# Output.net
KiCad netlist of a schematic drawn in Altium Designer
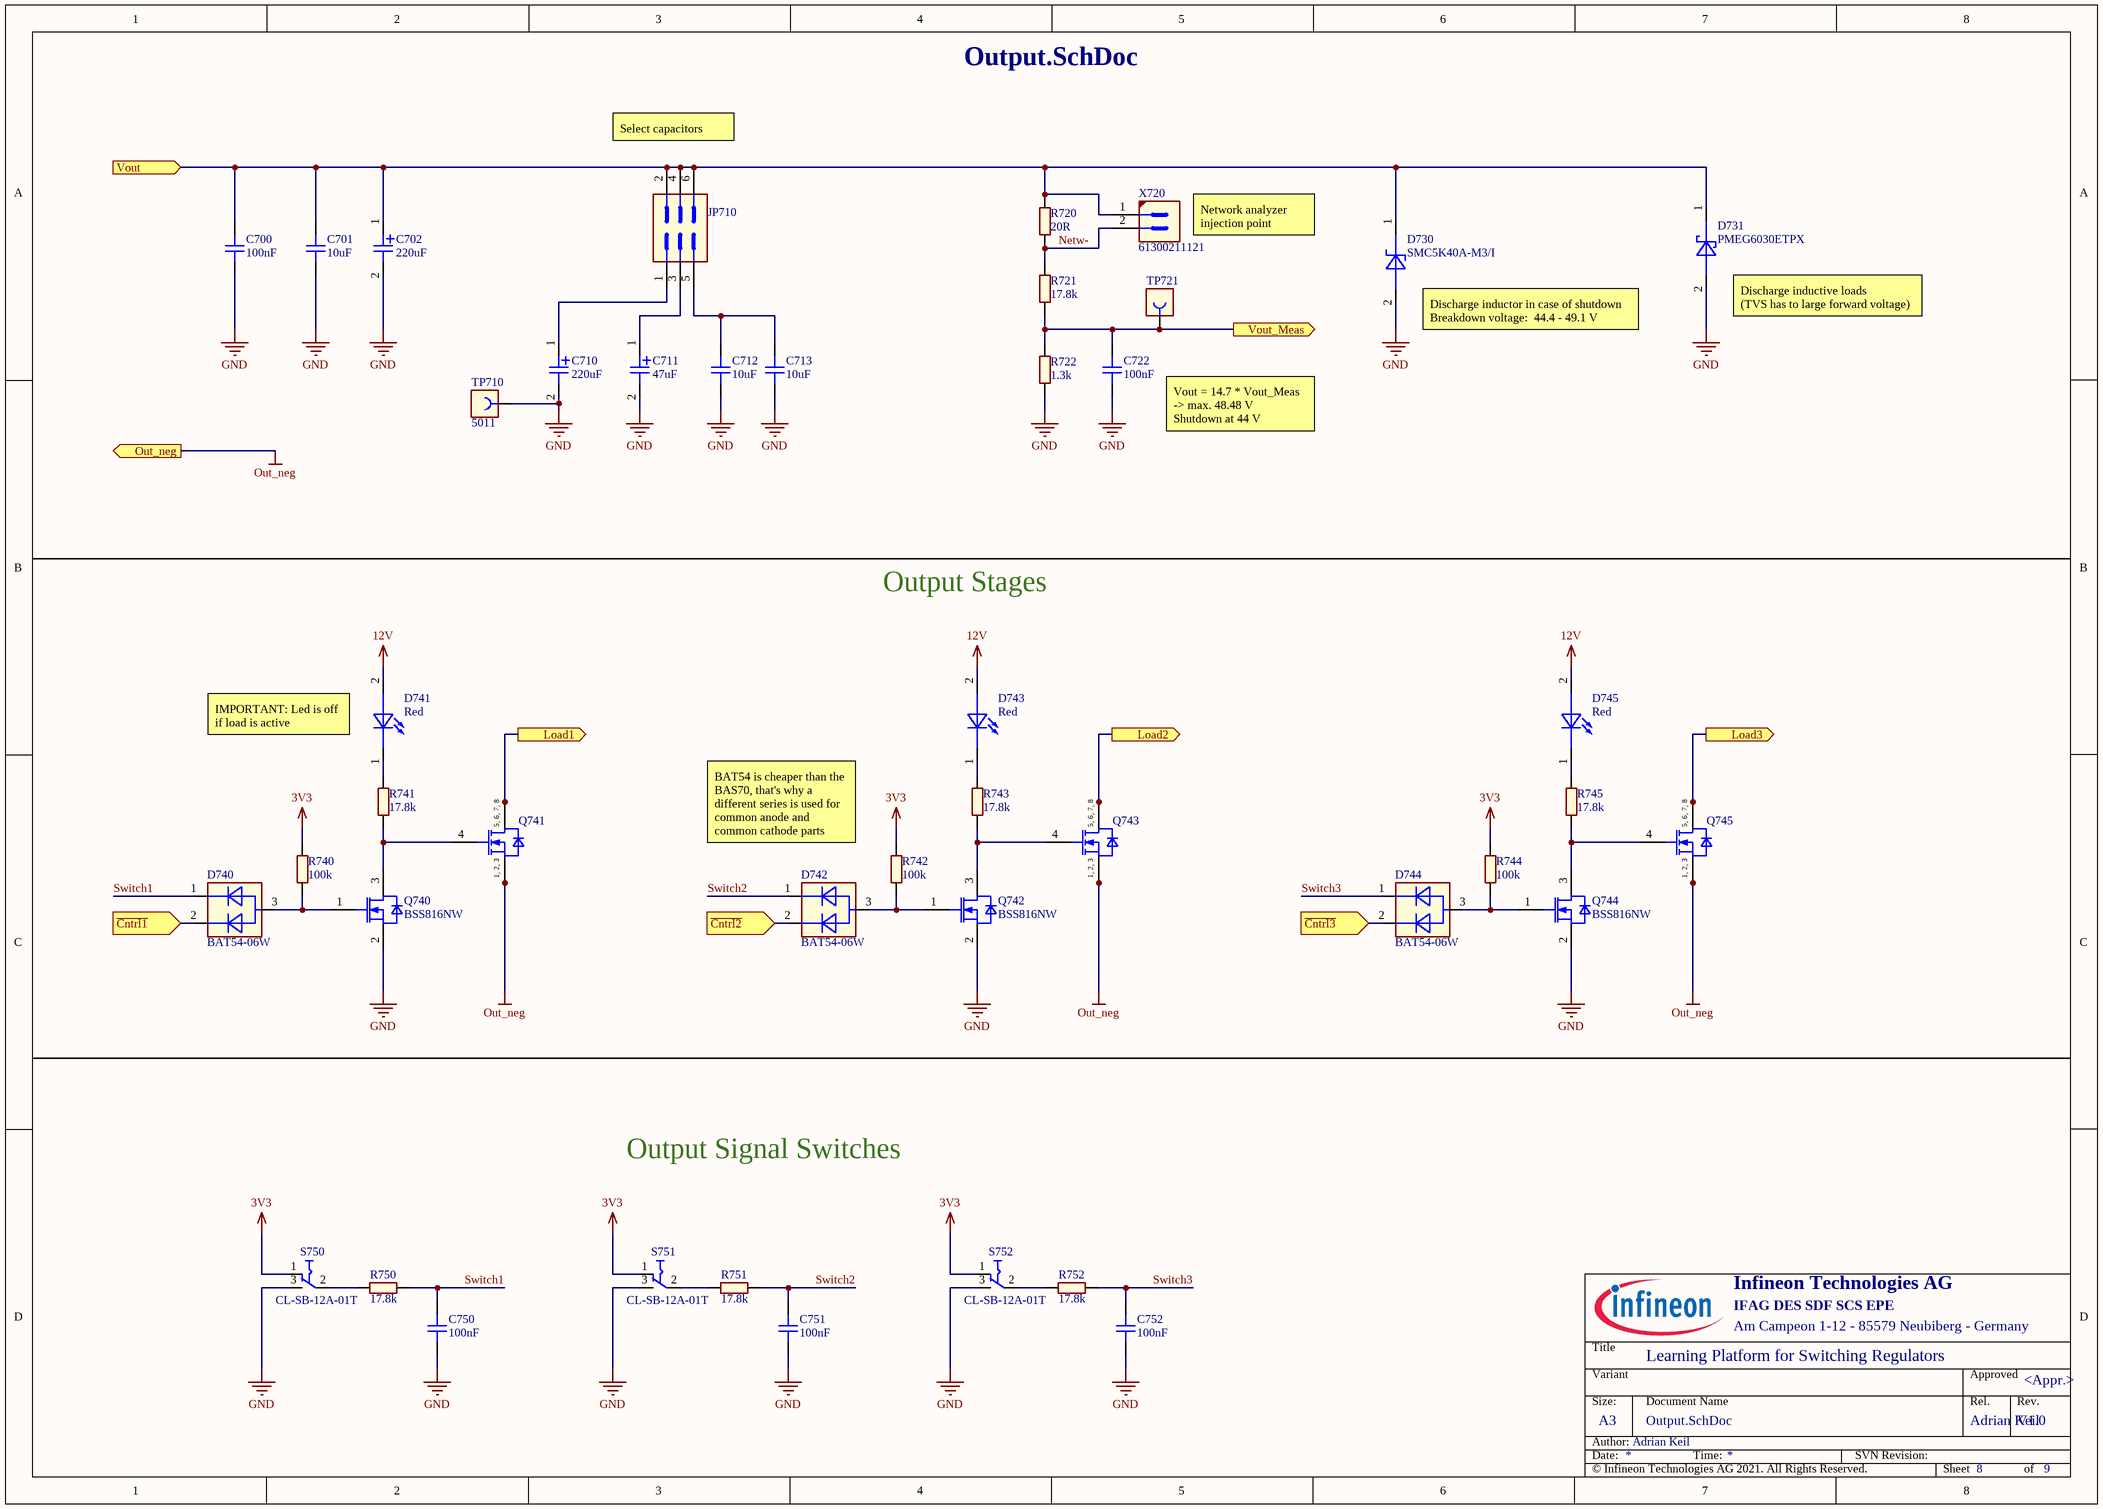
[diagram p0: Output.SchDoc]

(export (version "E")
  (design (tool "Eeschema 10.0.6"))
  (components
    (comp (ref "C700")
      (value "100nF")
      (footprint "CAPC1608X90N-2")
      (description "CAP / CERA / 100nF / 50V / 10% / X7R (EIA) / -55°C to 125°C / 0603 / SMD / -")
      (fields (field (name "MANUFACTURER") "AVX"))
      (libsource (lib "PCBLibraryData") (part "CAP-SGL-STD-02P_00000001"))
    )
    (comp (ref "C701")
      (value "10uF")
      (footprint "CAPC3216X190N-1")
      (description "CAP / CERA / 10uF / 50V / 20% / X5R (EIA) / -55°C to 85°C / 1206 (3216) / SMD / -")
      (fields (field (name "MANUFACTURER") "Taiyo Yuden"))
      (libsource (lib "PCBLibraryData") (part "CAP-SGL-STD-02P_00000001"))
    )
    (comp (ref "C702")
      (value "220uF")
      (footprint "CAPAE1030X1050N-2")
      (fields (field (name "MANUFACTURER") "Wurth Elektronik"))
      (libsource (lib "PCBLibraryData") (part "CAP-SGL-POL-02P_00000002"))
    )
    (comp (ref "C710")
      (value "220uF")
      (footprint "CAPAE1030X1050N-2")
      (fields (field (name "MANUFACTURER") "Wurth Elektronik"))
      (libsource (lib "PCBLibraryData") (part "CAP-SGL-POL-02P_00000002"))
    )
    (comp (ref "C711")
      (value "47uF")
      (footprint "CAPAE660X770N")
      (fields (field (name "MANUFACTURER") "Wurth Elektronik"))
      (libsource (lib "PCBLibraryData") (part "CAP-SGL-POL-02P_00000002"))
    )
    (comp (ref "C712")
      (value "10uF")
      (footprint "CAPC3216X190N-1")
      (description "CAP / CERA / 10uF / 50V / 20% / X5R (EIA) / -55°C to 85°C / 1206 (3216) / SMD / -")
      (fields (field (name "MANUFACTURER") "Taiyo Yuden"))
      (libsource (lib "PCBLibraryData") (part "CAP-SGL-STD-02P_00000001"))
    )
    (comp (ref "C713")
      (value "10uF")
      (footprint "CAPC3216X190N-1")
      (description "CAP / CERA / 10uF / 50V / 20% / X5R (EIA) / -55°C to 85°C / 1206 (3216) / SMD / -")
      (fields (field (name "MANUFACTURER") "Taiyo Yuden"))
      (libsource (lib "PCBLibraryData") (part "CAP-SGL-STD-02P_00000001"))
    )
    (comp (ref "C722")
      (value "100nF")
      (footprint "CAPC1608X90N-2")
      (description "CAP / CERA / 100nF / 50V / 10% / X7R (EIA) / -55°C to 125°C / 0603 / SMD / -")
      (fields (field (name "MANUFACTURER") "AVX"))
      (libsource (lib "PCBLibraryData") (part "CAP-SGL-STD-02P_00000001"))
    )
    (comp (ref "C750")
      (value "100nF")
      (footprint "CAPC1608X90N-2")
      (description "CAP / CERA / 100nF / 50V / 10% / X7R (EIA) / -55°C to 125°C / 0603 / SMD / -")
      (fields (field (name "MANUFACTURER") "AVX"))
      (libsource (lib "PCBLibraryData") (part "CAP-SGL-STD-02P_00000001"))
    )
    (comp (ref "C751")
      (value "100nF")
      (footprint "CAPC1608X90N-2")
      (description "CAP / CERA / 100nF / 50V / 10% / X7R (EIA) / -55°C to 125°C / 0603 / SMD / -")
      (fields (field (name "MANUFACTURER") "AVX"))
      (libsource (lib "PCBLibraryData") (part "CAP-SGL-STD-02P_00000001"))
    )
    (comp (ref "C752")
      (value "100nF")
      (footprint "CAPC1608X90N-2")
      (description "CAP / CERA / 100nF / 50V / 10% / X7R (EIA) / -55°C to 125°C / 0603 / SMD / -")
      (fields (field (name "MANUFACTURER") "AVX"))
      (libsource (lib "PCBLibraryData") (part "CAP-SGL-STD-02P_00000001"))
    )
    (comp (ref "D730")
      (value "SMC5K40A-M3/I")
      (footprint "DIOM7959X262N")
      (description "Surface Mount Transient Voltage Suppressors, Unidirectional, Very Fast Response Time")
      (fields (field (name "MANUFACTURER") "Vishay"))
      (libsource (lib "PCBLibraryData") (part "d_tvs_a"))
    )
    (comp (ref "D731")
      (value "PMEG6030ETPX")
      (footprint "SODFL4725X110N")
      (description "DIODE SCHOTTKY 60V 3A SOD128")
      (fields (field (name "MANUFACTURER") "Nexperia"))
      (libsource (lib "PCBLibraryData") (part "d_schottky_a"))
    )
    (comp (ref "D740")
      (value "BAT54-06W")
      (footprint "SOT65P210X100-3N-1-V")
      (description "Silicon Schottky Diodes")
      (fields (field (name "MANUFACTURER") "Infineon Technologies"))
      (libsource (lib "PCBLibraryData") (part "d_dual_c1c2a3_3p"))
    )
    (comp (ref "D741")
      (value "Red")
      (footprint "LEDSC160X80X80-2N-1")
      (description "WL-SMCW SMT Mono-color Chip LED Waterclear, Red,630nm")
      (fields (field (name "MANUFACTURER") "Wurth Elektronik"))
      (libsource (lib "PCBLibraryData") (part "d_led_a"))
    )
    (comp (ref "D742")
      (value "BAT54-06W")
      (footprint "SOT65P210X100-3N-1-V")
      (description "Silicon Schottky Diodes")
      (fields (field (name "MANUFACTURER") "Infineon Technologies"))
      (libsource (lib "PCBLibraryData") (part "d_dual_c1c2a3_3p"))
    )
    (comp (ref "D743")
      (value "Red")
      (footprint "LEDSC160X80X80-2N-1")
      (description "WL-SMCW SMT Mono-color Chip LED Waterclear, Red,630nm")
      (fields (field (name "MANUFACTURER") "Wurth Elektronik"))
      (libsource (lib "PCBLibraryData") (part "d_led_a"))
    )
    (comp (ref "D744")
      (value "BAT54-06W")
      (footprint "SOT65P210X100-3N-1-V")
      (description "Silicon Schottky Diodes")
      (fields (field (name "MANUFACTURER") "Infineon Technologies"))
      (libsource (lib "PCBLibraryData") (part "d_dual_c1c2a3_3p"))
    )
    (comp (ref "D745")
      (value "Red")
      (footprint "LEDSC160X80X80-2N-1")
      (description "WL-SMCW SMT Mono-color Chip LED Waterclear, Red,630nm")
      (fields (field (name "MANUFACTURER") "Wurth Elektronik"))
      (libsource (lib "PCBLibraryData") (part "d_led_a"))
    )
    (comp (ref "JP710")
      (value "Header 3X2A")
      (footprint "CON-M-THT-61300621121")
      (description "WR-PHD Dual Pin Header, 2.54mm Pitch, Double row, 6 Pins")
      (fields (field (name "MANUFACTURER") "Wurth Elektronik"))
      (libsource (lib "PCBLibraryData") (part "Header 3X2A"))
    )
    (comp (ref "Q740")
      (value "BSS816NW")
      (footprint "SOT65P210X100-3N-1-V")
      (description "OptiMOS 2 Small-Signal-Transistor")
      (fields (field (name "MANUFACTURER") "Infineon Technologies"))
      (libsource (lib "PCBLibraryData") (part "igfet_n_ch_dep_dio_1g2s3d_3p"))
    )
    (comp (ref "Q741")
      (value "igfet_n_ch_enh_dio_1s2s3s4g5d6d7d8d_8p")
      (footprint "INF-PG-TSDSON-8-FL")
      (description "OptiMOS Power - MOSFET, 60 V")
      (fields
        (field (name "LEGACY PARTNUMBER") "IFX01400359")
        (field (name "MANUFACTURER") "Infineon Technologies")
      )
      (libsource (lib "PCBLibraryData") (part "igfet_n_ch_enh_dio_1s2s3s4g5d6d7d8d_8p"))
    )
    (comp (ref "Q742")
      (value "BSS816NW")
      (footprint "SOT65P210X100-3N-1-V")
      (description "OptiMOS 2 Small-Signal-Transistor")
      (fields (field (name "MANUFACTURER") "Infineon Technologies"))
      (libsource (lib "PCBLibraryData") (part "igfet_n_ch_dep_dio_1g2s3d_3p"))
    )
    (comp (ref "Q743")
      (value "igfet_n_ch_enh_dio_1s2s3s4g5d6d7d8d_8p")
      (footprint "INF-PG-TSDSON-8-FL")
      (description "OptiMOS Power - MOSFET, 60 V")
      (fields
        (field (name "LEGACY PARTNUMBER") "IFX01400359")
        (field (name "MANUFACTURER") "Infineon Technologies")
      )
      (libsource (lib "PCBLibraryData") (part "igfet_n_ch_enh_dio_1s2s3s4g5d6d7d8d_8p"))
    )
    (comp (ref "Q744")
      (value "BSS816NW")
      (footprint "SOT65P210X100-3N-1-V")
      (description "OptiMOS 2 Small-Signal-Transistor")
      (fields (field (name "MANUFACTURER") "Infineon Technologies"))
      (libsource (lib "PCBLibraryData") (part "igfet_n_ch_dep_dio_1g2s3d_3p"))
    )
    (comp (ref "Q745")
      (value "igfet_n_ch_enh_dio_1s2s3s4g5d6d7d8d_8p")
      (footprint "INF-PG-TSDSON-8-FL")
      (description "OptiMOS Power - MOSFET, 60 V")
      (fields
        (field (name "LEGACY PARTNUMBER") "IFX01400359")
        (field (name "MANUFACTURER") "Infineon Technologies")
      )
      (libsource (lib "PCBLibraryData") (part "igfet_n_ch_enh_dio_1s2s3s4g5d6d7d8d_8p"))
    )
    (comp (ref "R720")
      (value "20R")
      (footprint "RESC1609X50N")
      (description "RES / STD / 20R / 100mW / 1% / 100ppm/K / -55°C to 155°C / 0603 / SMD / -")
      (fields (field (name "LEGACY PARTNUMBER") "RES01800947") (field (name "MANUFACTURER") "Vishay"))
      (libsource (lib "PCBLibraryData") (part "RES-SGL-STD-02P_00000006"))
    )
    (comp (ref "R721")
      (value "17.8k")
      (footprint "RESC1609X50N")
      (description "RES / STD / 17.8k / 100mW / 1% / 100ppm/K / -55°C to 155°C / 0603 / SMD / -")
      (fields (field (name "LEGACY PARTNUMBER") "RES01801283") (field (name "MANUFACTURER") "Vishay"))
      (libsource (lib "") (part "RES-SGL-STD-02P_00000006_1"))
    )
    (comp (ref "R722")
      (value "1.3k")
      (footprint "RESC1609X50N")
      (description "RES / STD / 1.3k / 100mW / 1% / 100ppm/K / -55°C to 155°C / 0603 / SMD / -")
      (fields (field (name "LEGACY PARTNUMBER") "RES01801155") (field (name "MANUFACTURER") "Vishay"))
      (libsource (lib "PCBLibraryData") (part "RES-SGL-STD-02P_00000006"))
    )
    (comp (ref "R740")
      (value "100k")
      (footprint "RESC1609X50N")
      (description "RES / STD / 100k / 100mW / 1% / 100ppm/K / -55°C to 155°C / 0603 / SMD / -")
      (fields (field (name "LEGACY PARTNUMBER") "RES01801371") (field (name "MANUFACTURER") "Vishay"))
      (libsource (lib "PCBLibraryData") (part "RES-SGL-STD-02P_00000006"))
    )
    (comp (ref "R741")
      (value "17.8k")
      (footprint "RESC1609X50N")
      (description "RES / STD / 17.8k / 100mW / 1% / 100ppm/K / -55°C to 155°C / 0603 / SMD / -")
      (fields (field (name "LEGACY PARTNUMBER") "RES01801283") (field (name "MANUFACTURER") "Vishay"))
      (libsource (lib "PCBLibraryData") (part "RES-SGL-STD-02P_00000006"))
    )
    (comp (ref "R742")
      (value "100k")
      (footprint "RESC1609X50N")
      (description "RES / STD / 100k / 100mW / 1% / 100ppm/K / -55°C to 155°C / 0603 / SMD / -")
      (fields (field (name "LEGACY PARTNUMBER") "RES01801371") (field (name "MANUFACTURER") "Vishay"))
      (libsource (lib "PCBLibraryData") (part "RES-SGL-STD-02P_00000006"))
    )
    (comp (ref "R743")
      (value "17.8k")
      (footprint "RESC1609X50N")
      (description "RES / STD / 17.8k / 100mW / 1% / 100ppm/K / -55°C to 155°C / 0603 / SMD / -")
      (fields (field (name "LEGACY PARTNUMBER") "RES01801283") (field (name "MANUFACTURER") "Vishay"))
      (libsource (lib "PCBLibraryData") (part "RES-SGL-STD-02P_00000006"))
    )
    (comp (ref "R744")
      (value "100k")
      (footprint "RESC1609X50N")
      (description "RES / STD / 100k / 100mW / 1% / 100ppm/K / -55°C to 155°C / 0603 / SMD / -")
      (fields (field (name "LEGACY PARTNUMBER") "RES01801371") (field (name "MANUFACTURER") "Vishay"))
      (libsource (lib "PCBLibraryData") (part "RES-SGL-STD-02P_00000006"))
    )
    (comp (ref "R745")
      (value "17.8k")
      (footprint "RESC1609X50N")
      (description "RES / STD / 17.8k / 100mW / 1% / 100ppm/K / -55°C to 155°C / 0603 / SMD / -")
      (fields (field (name "LEGACY PARTNUMBER") "RES01801283") (field (name "MANUFACTURER") "Vishay"))
      (libsource (lib "PCBLibraryData") (part "RES-SGL-STD-02P_00000006"))
    )
    (comp (ref "R750")
      (value "17.8k")
      (footprint "RESC1609X50N")
      (description "RES / STD / 17.8k / 100mW / 1% / 100ppm/K / -55°C to 155°C / 0603 / SMD / -")
      (fields (field (name "LEGACY PARTNUMBER") "RES01801283") (field (name "MANUFACTURER") "Vishay"))
      (libsource (lib "") (part "RES-SGL-STD-02P_00000006_2"))
    )
    (comp (ref "R751")
      (value "17.8k")
      (footprint "RESC1609X50N")
      (description "RES / STD / 17.8k / 100mW / 1% / 100ppm/K / -55°C to 155°C / 0603 / SMD / -")
      (fields (field (name "LEGACY PARTNUMBER") "RES01801283") (field (name "MANUFACTURER") "Vishay"))
      (libsource (lib "") (part "RES-SGL-STD-02P_00000006_2"))
    )
    (comp (ref "R752")
      (value "17.8k")
      (footprint "RESC1609X50N")
      (description "RES / STD / 17.8k / 100mW / 1% / 100ppm/K / -55°C to 155°C / 0603 / SMD / -")
      (fields (field (name "LEGACY PARTNUMBER") "RES01801283") (field (name "MANUFACTURER") "Vishay"))
      (libsource (lib "") (part "RES-SGL-STD-02P_00000006_2"))
    )
    (comp (ref "S750")
      (value "CL-SB-12A-01T")
      (footprint "SW-SMD-CL-SB-12A-01T")
      (description "Slid Switch, 12V, 200mA")
      (fields (field (name "MANUFACTURER") "NIDEC COPAL ELECTRONICS, Inc."))
      (libsource (lib "PCBLibraryData") (part "sw_co213_3p"))
    )
    (comp (ref "S751")
      (value "CL-SB-12A-01T")
      (footprint "SW-SMD-CL-SB-12A-01T")
      (description "Slid Switch, 12V, 200mA")
      (fields (field (name "MANUFACTURER") "NIDEC COPAL ELECTRONICS, Inc."))
      (libsource (lib "PCBLibraryData") (part "sw_co213_3p"))
    )
    (comp (ref "S752")
      (value "CL-SB-12A-01T")
      (footprint "SW-SMD-CL-SB-12A-01T")
      (description "Slid Switch, 12V, 200mA")
      (fields (field (name "MANUFACTURER") "NIDEC COPAL ELECTRONICS, Inc."))
      (libsource (lib "PCBLibraryData") (part "sw_co213_3p"))
    )
    (comp (ref "TP710")
      (value "5011")
      (footprint "CON-THT-TP-5011")
      (description "PC Test Point-Multipurpose THT, Black")
      (fields
        (field (name "LEGACY PARTNUMBER") "CON01500530")
        (field (name "MANUFACTURER") "Keystone Electronics Corp.")
      )
      (libsource (lib "PCBLibraryData") (part "connector_1_f"))
    )
    (comp (ref "TP721")
      (value "S1751-46R")
      (footprint "CON-SMD-TT-S1751-46")
      (description "Test Terminal, Surface Mount (Tape and Reeled Components)")
      (fields (field (name "LEGACY PARTNUMBER") "CON01501015") (field (name "MANUFACTURER") "Harwin"))
      (libsource (lib "") (part "connector_1_f_1"))
    )
    (comp (ref "X720")
      (value "61300211121")
      (footprint "CON-M-THT-61300211121")
      (description "Header, 2.54mm Pitch, 2 pin, Vertical, Single Row")
      (fields
        (field (name "LEGACY PARTNUMBER") "CON01500943")
        (field (name "MANUFACTURER") "Wurth Elektronik")
      )
      (libsource (lib "PCBLibraryData") (part "Header 2"))
    )
  )
  (nets
    (net (code "1") (name "/Cntrl1") (class "Default")
      (node (ref "D740") (pin "2") (pinfunction "CATHODE2_2") (pintype "passive"))
    )
    (net (code "2") (name "/Cntrl2") (class "Default")
      (node (ref "D742") (pin "2") (pinfunction "CATHODE2_2") (pintype "passive"))
    )
    (net (code "3") (name "/Cntrl3") (class "Default")
      (node (ref "D744") (pin "2") (pinfunction "CATHODE2_2") (pintype "passive"))
    )
    (net (code "4") (name "/Load1") (class "Default")
      (node (ref "Q741") (pin "5") (pinfunction "DRAIN_5") (pintype "passive"))
      (node (ref "Q741") (pin "6") (pinfunction "DRAIN_6") (pintype "passive"))
      (node (ref "Q741") (pin "7") (pinfunction "DRAIN_7") (pintype "passive"))
      (node (ref "Q741") (pin "8") (pinfunction "DRAIN_8") (pintype "passive"))
    )
    (net (code "5") (name "/Load2") (class "Default")
      (node (ref "Q743") (pin "5") (pinfunction "DRAIN_5") (pintype "passive"))
      (node (ref "Q743") (pin "6") (pinfunction "DRAIN_6") (pintype "passive"))
      (node (ref "Q743") (pin "7") (pinfunction "DRAIN_7") (pintype "passive"))
      (node (ref "Q743") (pin "8") (pinfunction "DRAIN_8") (pintype "passive"))
    )
    (net (code "6") (name "/Load3") (class "Default")
      (node (ref "Q745") (pin "5") (pinfunction "DRAIN_5") (pintype "passive"))
      (node (ref "Q745") (pin "6") (pinfunction "DRAIN_6") (pintype "passive"))
      (node (ref "Q745") (pin "7") (pinfunction "DRAIN_7") (pintype "passive"))
      (node (ref "Q745") (pin "8") (pinfunction "DRAIN_8") (pintype "passive"))
    )
    (net (code "7") (name "/Netw-") (class "Default")
      (node (ref "R720") (pin "1") (pinfunction "1_1") (pintype "passive"))
      (node (ref "R721") (pin "1") (pinfunction "1_1") (pintype "passive"))
      (node (ref "X720") (pin "2") (pinfunction "2_2") (pintype "passive"))
    )
    (net (code "8") (name "/Switch1") (class "Default")
      (node (ref "C750") (pin "2") (pinfunction "2_2") (pintype "passive"))
      (node (ref "D740") (pin "1") (pinfunction "CATHODE1_1") (pintype "passive"))
      (node (ref "R750") (pin "1") (pinfunction "1_1") (pintype "passive"))
    )
    (net (code "9") (name "/Switch2") (class "Default")
      (node (ref "C751") (pin "2") (pinfunction "2_2") (pintype "passive"))
      (node (ref "D742") (pin "1") (pinfunction "CATHODE1_1") (pintype "passive"))
      (node (ref "R751") (pin "1") (pinfunction "1_1") (pintype "passive"))
    )
    (net (code "10") (name "/Switch3") (class "Default")
      (node (ref "C752") (pin "2") (pinfunction "2_2") (pintype "passive"))
      (node (ref "D744") (pin "1") (pinfunction "CATHODE1_1") (pintype "passive"))
      (node (ref "R752") (pin "1") (pinfunction "1_1") (pintype "passive"))
    )
    (net (code "11") (name "/Vout") (class "Default")
      (node (ref "C700") (pin "2") (pinfunction "2_2") (pintype "passive"))
      (node (ref "C701") (pin "2") (pinfunction "2_2") (pintype "passive"))
      (node (ref "C702") (pin "1") (pinfunction "1_1") (pintype "passive"))
      (node (ref "D730") (pin "1") (pinfunction "CATHODE_1") (pintype "passive"))
      (node (ref "D731") (pin "1") (pinfunction "Cathode_1") (pintype "passive"))
      (node (ref "JP710") (pin "2") (pinfunction "2_2") (pintype "passive"))
      (node (ref "JP710") (pin "4") (pinfunction "4_4") (pintype "passive"))
      (node (ref "JP710") (pin "6") (pinfunction "6_6") (pintype "passive"))
      (node (ref "R720") (pin "2") (pinfunction "2_2") (pintype "passive"))
      (node (ref "X720") (pin "1") (pinfunction "1_1") (pintype "passive"))
    )
    (net (code "12") (name "/Vout_Meas") (class "Default")
      (node (ref "C722") (pin "2") (pinfunction "2_2") (pintype "passive"))
      (node (ref "R721") (pin "2") (pinfunction "2_2") (pintype "passive"))
      (node (ref "R722") (pin "2") (pinfunction "2_2") (pintype "passive"))
      (node (ref "TP721") (pin "1") (pinfunction "1_1") (pintype "passive"))
    )
    (net (code "13") (name "3V3") (class "Default")
      (node (ref "R740") (pin "2") (pinfunction "2_2") (pintype "passive"))
      (node (ref "R742") (pin "2") (pinfunction "2_2") (pintype "passive"))
      (node (ref "R744") (pin "2") (pinfunction "2_2") (pintype "passive"))
      (node (ref "S750") (pin "1") (pinfunction "1_1") (pintype "passive"))
      (node (ref "S751") (pin "1") (pinfunction "1_1") (pintype "passive"))
      (node (ref "S752") (pin "1") (pinfunction "1_1") (pintype "passive"))
    )
    (net (code "14") (name "12V") (class "Default")
      (node (ref "D741") (pin "2") (pinfunction "Anode_2") (pintype "passive"))
      (node (ref "D743") (pin "2") (pinfunction "Anode_2") (pintype "passive"))
      (node (ref "D745") (pin "2") (pinfunction "Anode_2") (pintype "passive"))
    )
    (net (code "15") (name "GND") (class "Default")
      (node (ref "C700") (pin "1") (pinfunction "1_1") (pintype "passive"))
      (node (ref "C701") (pin "1") (pinfunction "1_1") (pintype "passive"))
      (node (ref "C702") (pin "2") (pinfunction "2_2") (pintype "passive"))
      (node (ref "C710") (pin "2") (pinfunction "2_2") (pintype "passive"))
      (node (ref "C711") (pin "2") (pinfunction "2_2") (pintype "passive"))
      (node (ref "C712") (pin "1") (pinfunction "1_1") (pintype "passive"))
      (node (ref "C713") (pin "1") (pinfunction "1_1") (pintype "passive"))
      (node (ref "C722") (pin "1") (pinfunction "1_1") (pintype "passive"))
      (node (ref "C750") (pin "1") (pinfunction "1_1") (pintype "passive"))
      (node (ref "C751") (pin "1") (pinfunction "1_1") (pintype "passive"))
      (node (ref "C752") (pin "1") (pinfunction "1_1") (pintype "passive"))
      (node (ref "D730") (pin "2") (pinfunction "ANODE_2") (pintype "passive"))
      (node (ref "D731") (pin "2") (pinfunction "Anode_2") (pintype "passive"))
      (node (ref "Q740") (pin "2") (pinfunction "SOURCE_2") (pintype "passive"))
      (node (ref "Q742") (pin "2") (pinfunction "SOURCE_2") (pintype "passive"))
      (node (ref "Q744") (pin "2") (pinfunction "SOURCE_2") (pintype "passive"))
      (node (ref "R722") (pin "1") (pinfunction "1_1") (pintype "passive"))
      (node (ref "S750") (pin "3") (pinfunction "3_3") (pintype "passive"))
      (node (ref "S751") (pin "3") (pinfunction "3_3") (pintype "passive"))
      (node (ref "S752") (pin "3") (pinfunction "3_3") (pintype "passive"))
      (node (ref "TP710") (pin "1") (pinfunction "1_1") (pintype "passive"))
    )
    (net (code "16") (name "Net-(C710-Pad1)") (class "Default")
      (node (ref "C710") (pin "1") (pinfunction "1_1") (pintype "passive"))
      (node (ref "JP710") (pin "1") (pinfunction "1_1") (pintype "passive"))
    )
    (net (code "17") (name "Net-(C711-Pad1)") (class "Default")
      (node (ref "C711") (pin "1") (pinfunction "1_1") (pintype "passive"))
      (node (ref "JP710") (pin "3") (pinfunction "3_3") (pintype "passive"))
    )
    (net (code "18") (name "Net-(C712-Pad2)") (class "Default")
      (node (ref "C712") (pin "2") (pinfunction "2_2") (pintype "passive"))
      (node (ref "C713") (pin "2") (pinfunction "2_2") (pintype "passive"))
      (node (ref "JP710") (pin "5") (pinfunction "5_5") (pintype "passive"))
    )
    (net (code "19") (name "Net-(D740-ANODE)") (class "Default")
      (node (ref "D740") (pin "3") (pinfunction "ANODE_3") (pintype "passive"))
      (node (ref "Q740") (pin "1") (pinfunction "GATE_1") (pintype "passive"))
      (node (ref "R740") (pin "1") (pinfunction "1_1") (pintype "passive"))
    )
    (net (code "20") (name "Net-(D741-Cathode)") (class "Default")
      (node (ref "D741") (pin "1") (pinfunction "Cathode_1") (pintype "passive"))
      (node (ref "R741") (pin "2") (pinfunction "2_2") (pintype "passive"))
    )
    (net (code "21") (name "Net-(D742-ANODE)") (class "Default")
      (node (ref "D742") (pin "3") (pinfunction "ANODE_3") (pintype "passive"))
      (node (ref "Q742") (pin "1") (pinfunction "GATE_1") (pintype "passive"))
      (node (ref "R742") (pin "1") (pinfunction "1_1") (pintype "passive"))
    )
    (net (code "22") (name "Net-(D743-Cathode)") (class "Default")
      (node (ref "D743") (pin "1") (pinfunction "Cathode_1") (pintype "passive"))
      (node (ref "R743") (pin "2") (pinfunction "2_2") (pintype "passive"))
    )
    (net (code "23") (name "Net-(D744-ANODE)") (class "Default")
      (node (ref "D744") (pin "3") (pinfunction "ANODE_3") (pintype "passive"))
      (node (ref "Q744") (pin "1") (pinfunction "GATE_1") (pintype "passive"))
      (node (ref "R744") (pin "1") (pinfunction "1_1") (pintype "passive"))
    )
    (net (code "24") (name "Net-(D745-Cathode)") (class "Default")
      (node (ref "D745") (pin "1") (pinfunction "Cathode_1") (pintype "passive"))
      (node (ref "R745") (pin "2") (pinfunction "2_2") (pintype "passive"))
    )
    (net (code "25") (name "Net-(Q740-DRAIN)") (class "Default")
      (node (ref "Q740") (pin "3") (pinfunction "DRAIN_3") (pintype "passive"))
      (node (ref "Q741") (pin "4") (pinfunction "GATE_4") (pintype "passive"))
      (node (ref "R741") (pin "1") (pinfunction "1_1") (pintype "passive"))
    )
    (net (code "26") (name "Net-(Q742-DRAIN)") (class "Default")
      (node (ref "Q742") (pin "3") (pinfunction "DRAIN_3") (pintype "passive"))
      (node (ref "Q743") (pin "4") (pinfunction "GATE_4") (pintype "passive"))
      (node (ref "R743") (pin "1") (pinfunction "1_1") (pintype "passive"))
    )
    (net (code "27") (name "Net-(Q744-DRAIN)") (class "Default")
      (node (ref "Q744") (pin "3") (pinfunction "DRAIN_3") (pintype "passive"))
      (node (ref "Q745") (pin "4") (pinfunction "GATE_4") (pintype "passive"))
      (node (ref "R745") (pin "1") (pinfunction "1_1") (pintype "passive"))
    )
    (net (code "28") (name "Net-(R750-Pad2)") (class "Default")
      (node (ref "R750") (pin "2") (pinfunction "2_2") (pintype "passive"))
      (node (ref "S750") (pin "2") (pinfunction "2_2") (pintype "passive"))
    )
    (net (code "29") (name "Net-(R751-Pad2)") (class "Default")
      (node (ref "R751") (pin "2") (pinfunction "2_2") (pintype "passive"))
      (node (ref "S751") (pin "2") (pinfunction "2_2") (pintype "passive"))
    )
    (net (code "30") (name "Net-(R752-Pad2)") (class "Default")
      (node (ref "R752") (pin "2") (pinfunction "2_2") (pintype "passive"))
      (node (ref "S752") (pin "2") (pinfunction "2_2") (pintype "passive"))
    )
    (net (code "31") (name "Out_neg") (class "Default")
      (node (ref "Q741") (pin "1") (pinfunction "SOURCE_1") (pintype "passive"))
      (node (ref "Q741") (pin "2") (pinfunction "SOURCE_2") (pintype "passive"))
      (node (ref "Q741") (pin "3") (pinfunction "SOURCE_3") (pintype "passive"))
      (node (ref "Q743") (pin "1") (pinfunction "SOURCE_1") (pintype "passive"))
      (node (ref "Q743") (pin "2") (pinfunction "SOURCE_2") (pintype "passive"))
      (node (ref "Q743") (pin "3") (pinfunction "SOURCE_3") (pintype "passive"))
      (node (ref "Q745") (pin "1") (pinfunction "SOURCE_1") (pintype "passive"))
      (node (ref "Q745") (pin "2") (pinfunction "SOURCE_2") (pintype "passive"))
      (node (ref "Q745") (pin "3") (pinfunction "SOURCE_3") (pintype "passive"))
    )
  )
)
